# Sheet1.net
KiCad netlist of a schematic drawn in Altium Designer
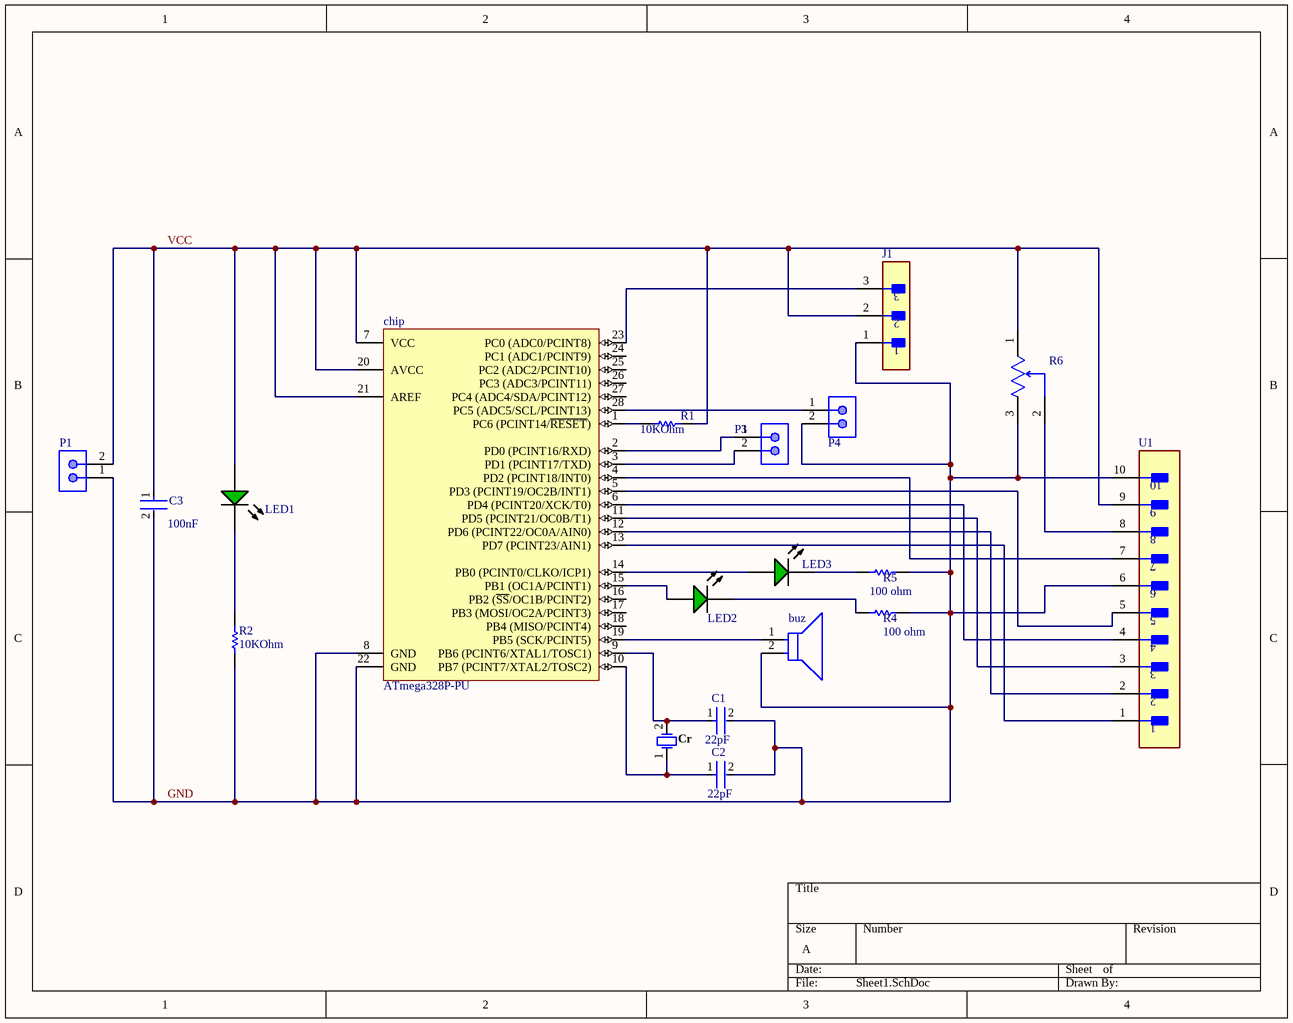
[diagram p0: Sheet1.SchDoc]

(export (version "E")
  (design (tool "Eeschema 10.0.6"))
  (components
    (comp (ref "buz")
      (value "PS1440P02BT")
      (footprint "FP-PS1440P02BT-MFG")
      (description "AUDIO PIEZO TRANSDUCER 30V TH")
      (libsource (lib "Altium Content Vault") (part "5f581d31613f872430949aa526fd155"))
    )
    (comp (ref "C1")
      (value "RCE5C2A220J0DBH03A")
      (footprint "FP-RCE0DB-MFG")
      (description "Cap Ceramic 22pF 100V C0G ±5% Radial 2.5mm +125°C Ammo Pack")
      (fields
        (field (name "VOLTAGE") "100V")
        (field (name "CAPACITANCE") "22pF")
        (field (name "TOLERANCE") "5%")
      )
      (libsource (lib "Altium Content Vault") (part "b4654b650e69147ec39a6b967a45e02"))
    )
    (comp (ref "C2")
      (value "RCE5C2A220J0DBH03A")
      (footprint "FP-RCE0DB-MFG")
      (description "Cap Ceramic 22pF 100V C0G ±5% Radial 2.5mm +125°C Ammo Pack")
      (fields
        (field (name "VOLTAGE") "100V")
        (field (name "CAPACITANCE") "22pF")
        (field (name "TOLERANCE") "5%")
      )
      (libsource (lib "Altium Content Vault") (part "b4654b650e69147ec39a6b967a45e02"))
    )
    (comp (ref "C3")
      (value "K104K15X7RF53H5")
      (footprint "FP-K15H5-MFG")
      (description "CAP CER 0.1UF 50V X7R RADIAL")
      (fields
        (field (name "CAPACITANCE") "100nF")
        (field (name "VOLTAGE") "50V")
        (field (name "TOLERANCE") "10%")
      )
      (libsource (lib "Altium Content Vault") (part "11868f565c42a9108669ba33697ecf6"))
    )
    (comp (ref "chip")
      (value "ATmega328P-PU")
      (footprint "28P3")
      (libsource (lib "Altium Content Vault") (part "MC-8B-ATM48-IL28"))
    )
    (comp (ref "Cr")
      (value "FOXSLF/160-20")
      (footprint "FOX-FOXSLF160-20")
      (description "Resistance Weld Thru-Hole Crystal, 16 MHz, -20 to 70 degC, 2-Pin THD, RoHS, Bulk")
      (fields (field (name "TOLERANCE") "1%"))
      (libsource (lib "Altium Content Vault") (part "XTAL-1-2-2"))
    )
    (comp (ref "J1")
      (value "TMM-103-03-T-S")
      (footprint "FP-TMM-103-03-T-S-MFG")
      (description "CONN HEADER VERT 3POS 2MM")
      (libsource (lib "Altium Content Vault") (part "0d3f023dd272f625e17a2be33dea85f"))
    )
    (comp (ref "LED1")
      (value "HLMP-1790")
      (footprint "LED-2P-2.54-3MM_V")
      (description "LED, Green, 2 mA, 1.9 V, -20 to 100 degC, 2-Pin THD, RoHS, Bulk")
      (fields (field (name "MANUFACTURER") "Avago"))
      (libsource (lib "Altium Content Vault") (part "LED_GREEN_A1K2-2"))
    )
    (comp (ref "LED2")
      (value "HLMP-1790")
      (footprint "LED-2P-2.54-3MM_V")
      (description "LED, Green, 2 mA, 1.9 V, -20 to 100 degC, 2-Pin THD, RoHS, Bulk")
      (fields (field (name "MANUFACTURER") "Avago"))
      (libsource (lib "Altium Content Vault") (part "LED_GREEN_A1K2-2"))
    )
    (comp (ref "LED3")
      (value "HLMP-1790")
      (footprint "LED-2P-2.54-3MM_V")
      (description "LED, Green, 2 mA, 1.9 V, -20 to 100 degC, 2-Pin THD, RoHS, Bulk")
      (fields (field (name "MANUFACTURER") "Avago"))
      (libsource (lib "Altium Content Vault") (part "LED_GREEN_A1K2-2"))
    )
    (comp (ref "P1")
      (value "22-27-2021")
      (footprint "MOLX-22-27-2021_V")
      (fields (field (name "MANUFACTURER") "Molex") (field (name "PARTNUMBER") "0022272021"))
      (libsource (lib "") (part "CN-1P-M-R2_1"))
    )
    (comp (ref "P3")
      (value "22-27-2021")
      (footprint "MOLX-22-27-2021_V")
      (fields (field (name "MANUFACTURER") "Molex") (field (name "PARTNUMBER") "0022272021"))
      (libsource (lib "Altium Content Vault") (part "CN-1P-M-R2"))
    )
    (comp (ref "P4")
      (value "22-27-2021")
      (footprint "MOLX-22-27-2021_V")
      (fields (field (name "MANUFACTURER") "Molex") (field (name "PARTNUMBER") "0022272021"))
      (libsource (lib "Altium Content Vault") (part "CN-1P-M-R2"))
    )
    (comp (ref "R1")
      (value "MFR-25FBF5210K")
      (footprint "RESA60-630X240")
      (description "Axial Resistor, 10 KOhm, +/- 1%, 0.25 W, -55 to 155 degC, 2-Pin THD, RoHS, Bulk")
      (fields
        (field (name "RESISTANCE") "10KOhm")
        (field (name "TOLERANCE") "1%")
        (field (name "MANUFACTURER") "Yageo")
      )
      (libsource (lib "Altium Content Vault") (part "RES-2"))
    )
    (comp (ref "R2")
      (value "MFR-25FBF5210K")
      (footprint "RESA60-630X240")
      (description "Axial Resistor, 10 KOhm, +/- 1%, 0.25 W, -55 to 155 degC, 2-Pin THD, RoHS, Bulk")
      (fields
        (field (name "RESISTANCE") "10KOhm")
        (field (name "TOLERANCE") "1%")
        (field (name "MANUFACTURER") "Yageo")
      )
      (libsource (lib "Altium Content Vault") (part "RES-2"))
    )
    (comp (ref "R4")
      (value "MFR-25FBF52-1K")
      (footprint "RESA60-630X240")
      (description "Axial Resistor, 1 KOhm, +/- 1%, 250 mW, -55 to 155 degC, 2-Pin THD, RoHS, Bulk")
      (fields (field (name "TOLERANCE") "1%") (field (name "RESISTANCE") "100 ohm"))
      (libsource (lib "Altium Content Vault") (part "RES-2"))
    )
    (comp (ref "R5")
      (value "MFR-25FBF52-1K")
      (footprint "RESA60-630X240")
      (description "Axial Resistor, 1 KOhm, +/- 1%, 250 mW, -55 to 155 degC, 2-Pin THD, RoHS, Bulk")
      (fields (field (name "TOLERANCE") "1%") (field (name "RESISTANCE") "100 ohm"))
      (libsource (lib "Altium Content Vault") (part "RES-2"))
    )
    (comp (ref "R6")
      (value "3296W-1-202LF")
      (footprint "FP-3296W-MFG")
      (description "TRIMMER 2K OHM 0.5W PC PIN TOP")
      (fields (field (name "TOLERANCE") "10%"))
      (libsource (lib "Altium Content Vault") (part "81a8d1f2e6c155a1fa928b358d1a42a"))
    )
    (comp (ref "U1")
      (value "61301011121")
      (footprint "FP-61301011121-MFG")
      (description "CONN HEADER VERT 10POS 2.54MM")
      (libsource (lib "Altium Content Vault") (part "aee40dc8b284c03a16094555aa210be"))
    )
  )
  (nets
    (net (code "1") (name "/GND") (class "Default")
      (node (ref "C1") (pin "2") (pinfunction "2_2") (pintype "passive"))
      (node (ref "C2") (pin "2") (pinfunction "2_2") (pintype "passive"))
      (node (ref "C3") (pin "2") (pinfunction "2_2") (pintype "passive"))
      (node (ref "J1") (pin "1") (pinfunction "1_1") (pintype "passive"))
      (node (ref "P1") (pin "1") (pinfunction "1_1") (pintype "passive"))
      (node (ref "P4") (pin "2") (pinfunction "2_2") (pintype "passive"))
      (node (ref "R2") (pin "1") (pinfunction "1_1") (pintype "passive"))
      (node (ref "R4") (pin "2") (pinfunction "2_2") (pintype "passive"))
      (node (ref "R5") (pin "2") (pinfunction "2_2") (pintype "passive"))
      (node (ref "R6") (pin "3") (pinfunction "CW_3") (pintype "passive"))
      (node (ref "U1") (pin "10") (pinfunction "10_10") (pintype "passive"))
      (node (ref "U1") (pin "6") (pinfunction "6_6") (pintype "passive"))
      (node (ref "buz") (pin "2") (pinfunction "2_2") (pintype "passive"))
      (node (ref "chip") (pin "22") (pinfunction "GND_22") (pintype "power_in"))
      (node (ref "chip") (pin "8") (pinfunction "GND_8") (pintype "power_in"))
    )
    (net (code "2") (name "/VCC") (class "Default")
      (node (ref "C3") (pin "1") (pinfunction "1_1") (pintype "passive"))
      (node (ref "J1") (pin "2") (pinfunction "2_2") (pintype "passive"))
      (node (ref "LED1") (pin "1") (pinfunction "A_1") (pintype "passive"))
      (node (ref "P1") (pin "2") (pinfunction "2_2") (pintype "passive"))
      (node (ref "R1") (pin "2") (pinfunction "2_2") (pintype "passive"))
      (node (ref "R6") (pin "1") (pinfunction "CCW_1") (pintype "passive"))
      (node (ref "U1") (pin "9") (pinfunction "9_9") (pintype "passive"))
      (node (ref "chip") (pin "20") (pinfunction "AVCC_20") (pintype "power_in"))
      (node (ref "chip") (pin "21") (pinfunction "AREF_21") (pintype "power_in"))
      (node (ref "chip") (pin "7") (pinfunction "VCC_7") (pintype "power_in"))
    )
    (net (code "3") (name "Net-(LED1-K)") (class "Default")
      (node (ref "LED1") (pin "2") (pinfunction "K_2") (pintype "passive"))
      (node (ref "R2") (pin "2") (pinfunction "2_2") (pintype "passive"))
    )
    (net (code "4") (name "Net-(LED2-A)") (class "Default")
      (node (ref "LED2") (pin "1") (pinfunction "A_1") (pintype "passive"))
      (node (ref "chip") (pin "15") (pinfunction "PB1_(OC1A/PCINT1)_15") (pintype "bidirectional"))
    )
    (net (code "5") (name "Net-(LED2-K)") (class "Default")
      (node (ref "LED2") (pin "2") (pinfunction "K_2") (pintype "passive"))
      (node (ref "R4") (pin "1") (pinfunction "1_1") (pintype "passive"))
    )
    (net (code "6") (name "Net-(LED3-A)") (class "Default")
      (node (ref "LED3") (pin "1") (pinfunction "A_1") (pintype "passive"))
      (node (ref "chip") (pin "14") (pinfunction "PB0_(PCINT0/CLKO/ICP1)_14") (pintype "bidirectional"))
    )
    (net (code "7") (name "Net-(LED3-K)") (class "Default")
      (node (ref "LED3") (pin "2") (pinfunction "K_2") (pintype "passive"))
      (node (ref "R5") (pin "1") (pinfunction "1_1") (pintype "passive"))
    )
    (net (code "8") (name "Net-(R6-WIPER)") (class "Default")
      (node (ref "R6") (pin "2") (pinfunction "WIPER_2") (pintype "passive"))
      (node (ref "U1") (pin "8") (pinfunction "8_8") (pintype "passive"))
    )
    (net (code "9") (name "Net-(chip-PB5_(SCK{slash}PCINT5))") (class "Default")
      (node (ref "buz") (pin "1") (pinfunction "1_1") (pintype "passive"))
      (node (ref "chip") (pin "19") (pinfunction "PB5_(SCK/PCINT5)_19") (pintype "bidirectional"))
    )
    (net (code "10") (name "Net-(chip-PB6_(PCINT6{slash}XTAL1{slash}TOSC1))") (class "Default")
      (node (ref "C1") (pin "1") (pinfunction "1_1") (pintype "passive"))
      (node (ref "Cr") (pin "2") (pinfunction "2_2") (pintype "passive"))
      (node (ref "chip") (pin "9") (pinfunction "PB6_(PCINT6/XTAL1/TOSC1)_9") (pintype "bidirectional"))
    )
    (net (code "11") (name "Net-(chip-PB7_(PCINT7{slash}XTAL2{slash}TOSC2))") (class "Default")
      (node (ref "C2") (pin "1") (pinfunction "1_1") (pintype "passive"))
      (node (ref "Cr") (pin "1") (pinfunction "1_1") (pintype "passive"))
      (node (ref "chip") (pin "10") (pinfunction "PB7_(PCINT7/XTAL2/TOSC2)_10") (pintype "bidirectional"))
    )
    (net (code "12") (name "Net-(chip-PC0_(ADC0{slash}PCINT8))") (class "Default")
      (node (ref "J1") (pin "3") (pinfunction "3_3") (pintype "passive"))
      (node (ref "chip") (pin "23") (pinfunction "PC0_(ADC0/PCINT8)_23") (pintype "bidirectional"))
    )
    (net (code "13") (name "Net-(chip-PC5_(ADC5{slash}SCL{slash}PCINT13))") (class "Default")
      (node (ref "P4") (pin "1") (pinfunction "1_1") (pintype "passive"))
      (node (ref "chip") (pin "28") (pinfunction "PC5_(ADC5/SCL/PCINT13)_28") (pintype "bidirectional"))
    )
    (net (code "14") (name "Net-(chip-PC6_(PCINT14{slash}~{RESET}))") (class "Default")
      (node (ref "R1") (pin "1") (pinfunction "1_1") (pintype "passive"))
      (node (ref "chip") (pin "1") (pinfunction "PC6_(PCINT14/~{RESET})_1") (pintype "bidirectional"))
    )
    (net (code "15") (name "Net-(chip-PD0_(PCINT16{slash}RXD))") (class "Default")
      (node (ref "P3") (pin "1") (pinfunction "1_1") (pintype "passive"))
      (node (ref "chip") (pin "2") (pinfunction "PD0_(PCINT16/RXD)_2") (pintype "bidirectional"))
    )
    (net (code "16") (name "Net-(chip-PD1_(PCINT17{slash}TXD))") (class "Default")
      (node (ref "P3") (pin "2") (pinfunction "2_2") (pintype "passive"))
      (node (ref "chip") (pin "3") (pinfunction "PD1_(PCINT17/TXD)_3") (pintype "bidirectional"))
    )
    (net (code "17") (name "Net-(chip-PD2_(PCINT18{slash}INT0))") (class "Default")
      (node (ref "U1") (pin "7") (pinfunction "7_7") (pintype "passive"))
      (node (ref "chip") (pin "4") (pinfunction "PD2_(PCINT18/INT0)_4") (pintype "bidirectional"))
    )
    (net (code "18") (name "Net-(chip-PD3_(PCINT19{slash}OC2B{slash}INT1))") (class "Default")
      (node (ref "U1") (pin "5") (pinfunction "5_5") (pintype "passive"))
      (node (ref "chip") (pin "5") (pinfunction "PD3_(PCINT19/OC2B/INT1)_5") (pintype "bidirectional"))
    )
    (net (code "19") (name "Net-(chip-PD4_(PCINT20{slash}XCK{slash}T0))") (class "Default")
      (node (ref "U1") (pin "4") (pinfunction "4_4") (pintype "passive"))
      (node (ref "chip") (pin "6") (pinfunction "PD4_(PCINT20/XCK/T0)_6") (pintype "bidirectional"))
    )
    (net (code "20") (name "Net-(chip-PD5_(PCINT21{slash}OC0B{slash}T1))") (class "Default")
      (node (ref "U1") (pin "3") (pinfunction "3_3") (pintype "passive"))
      (node (ref "chip") (pin "11") (pinfunction "PD5_(PCINT21/OC0B/T1)_11") (pintype "bidirectional"))
    )
    (net (code "21") (name "Net-(chip-PD6_(PCINT22{slash}OC0A{slash}AIN0))") (class "Default")
      (node (ref "U1") (pin "2") (pinfunction "2_2") (pintype "passive"))
      (node (ref "chip") (pin "12") (pinfunction "PD6_(PCINT22/OC0A/AIN0)_12") (pintype "bidirectional"))
    )
    (net (code "22") (name "Net-(chip-PD7_(PCINT23{slash}AIN1))") (class "Default")
      (node (ref "U1") (pin "1") (pinfunction "1_1") (pintype "passive"))
      (node (ref "chip") (pin "13") (pinfunction "PD7_(PCINT23/AIN1)_13") (pintype "bidirectional"))
    )
    (net (code "23") (name "unconnected-(chip-PB2_(~{SS}{slash}OC1B{slash}PCINT2)-Pad16)") (class "Default")
      (node (ref "chip") (pin "16") (pinfunction "PB2_(~{SS}/OC1B/PCINT2)_16") (pintype "bidirectional"))
    )
    (net (code "24") (name "unconnected-(chip-PB3_(MOSI{slash}OC2A{slash}PCINT3)-Pad17)") (class "Default")
      (node (ref "chip") (pin "17") (pinfunction "PB3_(MOSI/OC2A/PCINT3)_17") (pintype "bidirectional"))
    )
    (net (code "25") (name "unconnected-(chip-PB4_(MISO{slash}PCINT4)-Pad18)") (class "Default")
      (node (ref "chip") (pin "18") (pinfunction "PB4_(MISO/PCINT4)_18") (pintype "bidirectional"))
    )
    (net (code "26") (name "unconnected-(chip-PC1_(ADC1{slash}PCINT9)-Pad24)") (class "Default")
      (node (ref "chip") (pin "24") (pinfunction "PC1_(ADC1/PCINT9)_24") (pintype "bidirectional"))
    )
    (net (code "27") (name "unconnected-(chip-PC2_(ADC2{slash}PCINT10)-Pad25)") (class "Default")
      (node (ref "chip") (pin "25") (pinfunction "PC2_(ADC2/PCINT10)_25") (pintype "bidirectional"))
    )
    (net (code "28") (name "unconnected-(chip-PC3_(ADC3{slash}PCINT11)-Pad26)") (class "Default")
      (node (ref "chip") (pin "26") (pinfunction "PC3_(ADC3/PCINT11)_26") (pintype "bidirectional"))
    )
    (net (code "29") (name "unconnected-(chip-PC4_(ADC4{slash}SDA{slash}PCINT12)-Pad27)") (class "Default")
      (node (ref "chip") (pin "27") (pinfunction "PC4_(ADC4/SDA/PCINT12)_27") (pintype "bidirectional"))
    )
  )
)
